# TriacSwitch.net
KiCad netlist of a schematic drawn in EAGLE
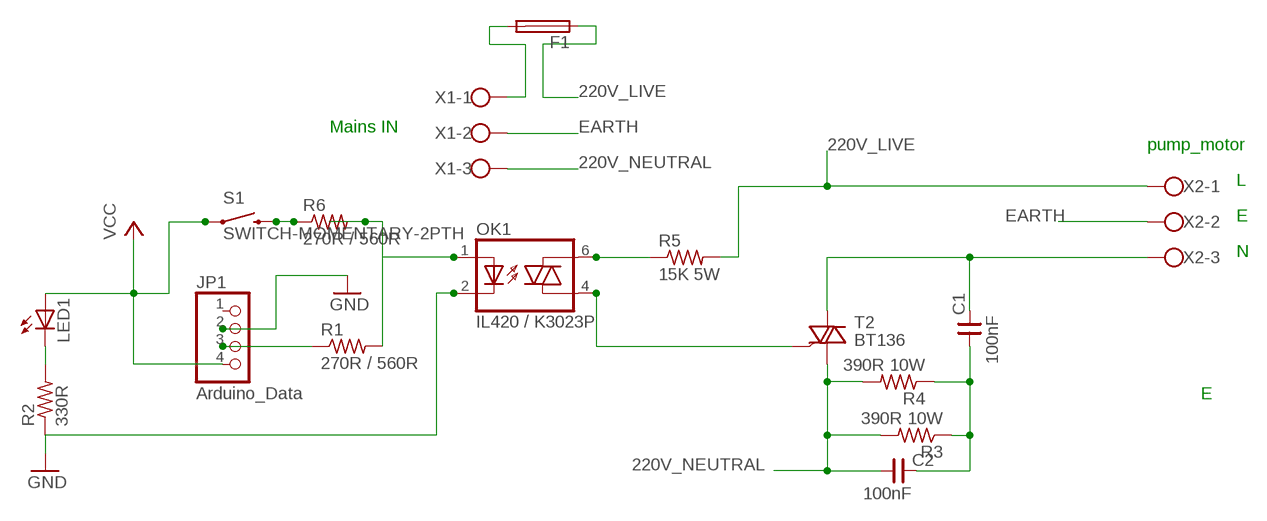
[diagram p0: schematic, sheet 1]

(export (version "E")
  (design (tool "Eeschema 10.0.6"))
  (components
    (comp (ref "C1")
      (value "100nF")
      (footprint "eagle-import:C050-110X055")
      (libsource (lib "eagle-import") (part "CNP-C050-110X055"))
    )
    (comp (ref "C2")
      (value "100nF")
      (footprint "eagle-import:C050-110X055")
      (libsource (lib "eagle-import") (part "CNP-C050-110X055"))
    )
    (comp (ref "F1")
      (value "KS10H")
      (footprint "eagle-import:KS10H")
      (libsource (lib "eagle-import") (part "KS10H"))
    )
    (comp (ref "JP1")
      (value "Arduino_Data")
      (footprint "eagle-import:1X04")
      (libsource (lib "eagle-import") (part "PINHD-1X4"))
    )
    (comp (ref "LED1")
      (value "LED3MM")
      (footprint "eagle-import:LED3MM")
      (libsource (lib "eagle-import") (part "LED3MM"))
    )
    (comp (ref "OK1")
      (value "IL420 / K3023P")
      (footprint "eagle-import:DIL06")
      (fields (field (name "MF") "VISHAY/TELEFUNKEN") (field (name "MPN") "IL420"))
      (libsource (lib "eagle-import") (part "IL420"))
    )
    (comp (ref "R1")
      (value "270R / 560R")
      (footprint "eagle-import:0207_10")
      (libsource (lib "eagle-import") (part "R-US_0207/10"))
    )
    (comp (ref "R2")
      (value "330R")
      (footprint "eagle-import:0207_10")
      (libsource (lib "eagle-import") (part "R-US_0207/10"))
    )
    (comp (ref "R3")
      (value "390R 10W")
      (footprint "eagle-import:0922_22")
      (libsource (lib "eagle-import") (part "R-US_0922/22"))
    )
    (comp (ref "R4")
      (value "390R 10W")
      (footprint "eagle-import:0922_22")
      (libsource (lib "eagle-import") (part "R-US_0922/22"))
    )
    (comp (ref "R5")
      (value "15K 5W")
      (footprint "eagle-import:0617_17")
      (libsource (lib "eagle-import") (part "R-US_0617/17"))
    )
    (comp (ref "R6")
      (value "270R / 560R")
      (footprint "eagle-import:0207_10")
      (libsource (lib "eagle-import") (part "R-US_0207/10"))
    )
    (comp (ref "S1")
      (value "SWITCH-MOMENTARY-2PTH")
      (footprint "eagle-import:TACTILE-PTH")
      (libsource (lib "eagle-import") (part "SWITCH-MOMENTARY-2PTH"))
    )
    (comp (ref "T2")
      (value "BT136")
      (footprint "eagle-import:TO220AB")
      (libsource (lib "eagle-import") (part "BT136"))
    )
    (comp (ref "X1")
      (value "W237-103")
      (footprint "eagle-import:W237-103")
      (fields (field (name "MPN") "237-103"))
      (libsource (lib "eagle-import") (part "W237-103"))
    )
    (comp (ref "X2")
      (value "W237-103")
      (footprint "eagle-import:W237-103")
      (fields (field (name "MPN") "237-103"))
      (libsource (lib "eagle-import") (part "W237-103"))
    )
  )
  (nets
    (net (code "1") (name "/220V_LIVE") (class "Default")
      (node (ref "F1") (pin "1") (pinfunction "1_1") (pintype "passive"))
      (node (ref "R5") (pin "2") (pinfunction "2_2") (pintype "passive"))
      (node (ref "X2") (pin "1") (pinfunction "KL_1") (pintype "passive"))
    )
    (net (code "2") (name "/220V_NEUTRAL") (class "Default")
      (node (ref "C2") (pin "1") (pinfunction "1_1") (pintype "passive"))
      (node (ref "R3") (pin "2") (pinfunction "2_2") (pintype "passive"))
      (node (ref "R4") (pin "2") (pinfunction "2_2") (pintype "passive"))
      (node (ref "T2") (pin "1") (pinfunction "A1_1") (pintype "passive"))
      (node (ref "X1") (pin "3") (pinfunction "KL_3") (pintype "passive"))
    )
    (net (code "3") (name "/EARTH") (class "Default")
      (node (ref "X1") (pin "2") (pinfunction "KL_2") (pintype "passive"))
      (node (ref "X2") (pin "2") (pinfunction "KL_2") (pintype "passive"))
    )
    (net (code "4") (name "GND") (class "Default")
      (node (ref "JP1") (pin "2") (pinfunction "2_2") (pintype "passive"))
      (node (ref "OK1") (pin "2") (pinfunction "C_2") (pintype "passive"))
      (node (ref "R2") (pin "1") (pinfunction "1_1") (pintype "passive"))
    )
    (net (code "5") (name "Net-(C1-Pad1)") (class "Default")
      (node (ref "C1") (pin "1") (pinfunction "1_1") (pintype "passive"))
      (node (ref "C2") (pin "2") (pinfunction "2_2") (pintype "passive"))
      (node (ref "R3") (pin "1") (pinfunction "1_1") (pintype "passive"))
      (node (ref "R4") (pin "1") (pinfunction "1_1") (pintype "passive"))
    )
    (net (code "6") (name "Net-(JP1-Pad3)") (class "Default")
      (node (ref "JP1") (pin "3") (pinfunction "3_3") (pintype "passive"))
      (node (ref "R1") (pin "1") (pinfunction "1_1") (pintype "passive"))
    )
    (net (code "7") (name "Net-(LED1-C)") (class "Default")
      (node (ref "LED1") (pin "K") (pinfunction "C_K") (pintype "passive"))
      (node (ref "R2") (pin "2") (pinfunction "2_2") (pintype "passive"))
    )
    (net (code "8") (name "Net-(OK1-A)") (class "Default")
      (node (ref "OK1") (pin "1") (pinfunction "A_1") (pintype "passive"))
      (node (ref "R1") (pin "2") (pinfunction "2_2") (pintype "passive"))
      (node (ref "R6") (pin "2") (pinfunction "2_2") (pintype "passive"))
    )
    (net (code "9") (name "Net-(OK1-A1)") (class "Default")
      (node (ref "OK1") (pin "4") (pinfunction "A1_4") (pintype "passive"))
      (node (ref "T2") (pin "3") (pinfunction "G_3") (pintype "passive"))
    )
    (net (code "10") (name "Net-(OK1-A2)") (class "Default")
      (node (ref "OK1") (pin "6") (pinfunction "A2_6") (pintype "passive"))
      (node (ref "R5") (pin "1") (pinfunction "1_1") (pintype "passive"))
    )
    (net (code "11") (name "Net-(S1-2)") (class "Default")
      (node (ref "R6") (pin "1") (pinfunction "1_1") (pintype "passive"))
      (node (ref "S1") (pin "3") (pinfunction "2_3") (pintype "passive"))
    )
    (net (code "12") (name "Net-(T2-A2)") (class "Default")
      (node (ref "C1") (pin "2") (pinfunction "2_2") (pintype "passive"))
      (node (ref "T2") (pin "2") (pinfunction "A2_2") (pintype "passive"))
      (node (ref "X2") (pin "3") (pinfunction "KL_3") (pintype "passive"))
    )
    (net (code "13") (name "Net-(X1A-KL)") (class "Default")
      (node (ref "F1") (pin "2") (pinfunction "2_2") (pintype "passive"))
      (node (ref "X1") (pin "1") (pinfunction "KL_1") (pintype "passive"))
    )
    (net (code "14") (name "VCC") (class "Default")
      (node (ref "JP1") (pin "4") (pinfunction "4_4") (pintype "passive"))
      (node (ref "LED1") (pin "A") (pinfunction "A_A") (pintype "passive"))
      (node (ref "S1") (pin "1") (pinfunction "1_1") (pintype "passive"))
    )
    (net (code "15") (name "unconnected-(JP1-Pad1)") (class "Default")
      (node (ref "JP1") (pin "1") (pinfunction "1_1") (pintype "passive"))
    )
  )
)
